# working.net
KiCad netlist of a schematic drawn in EAGLE
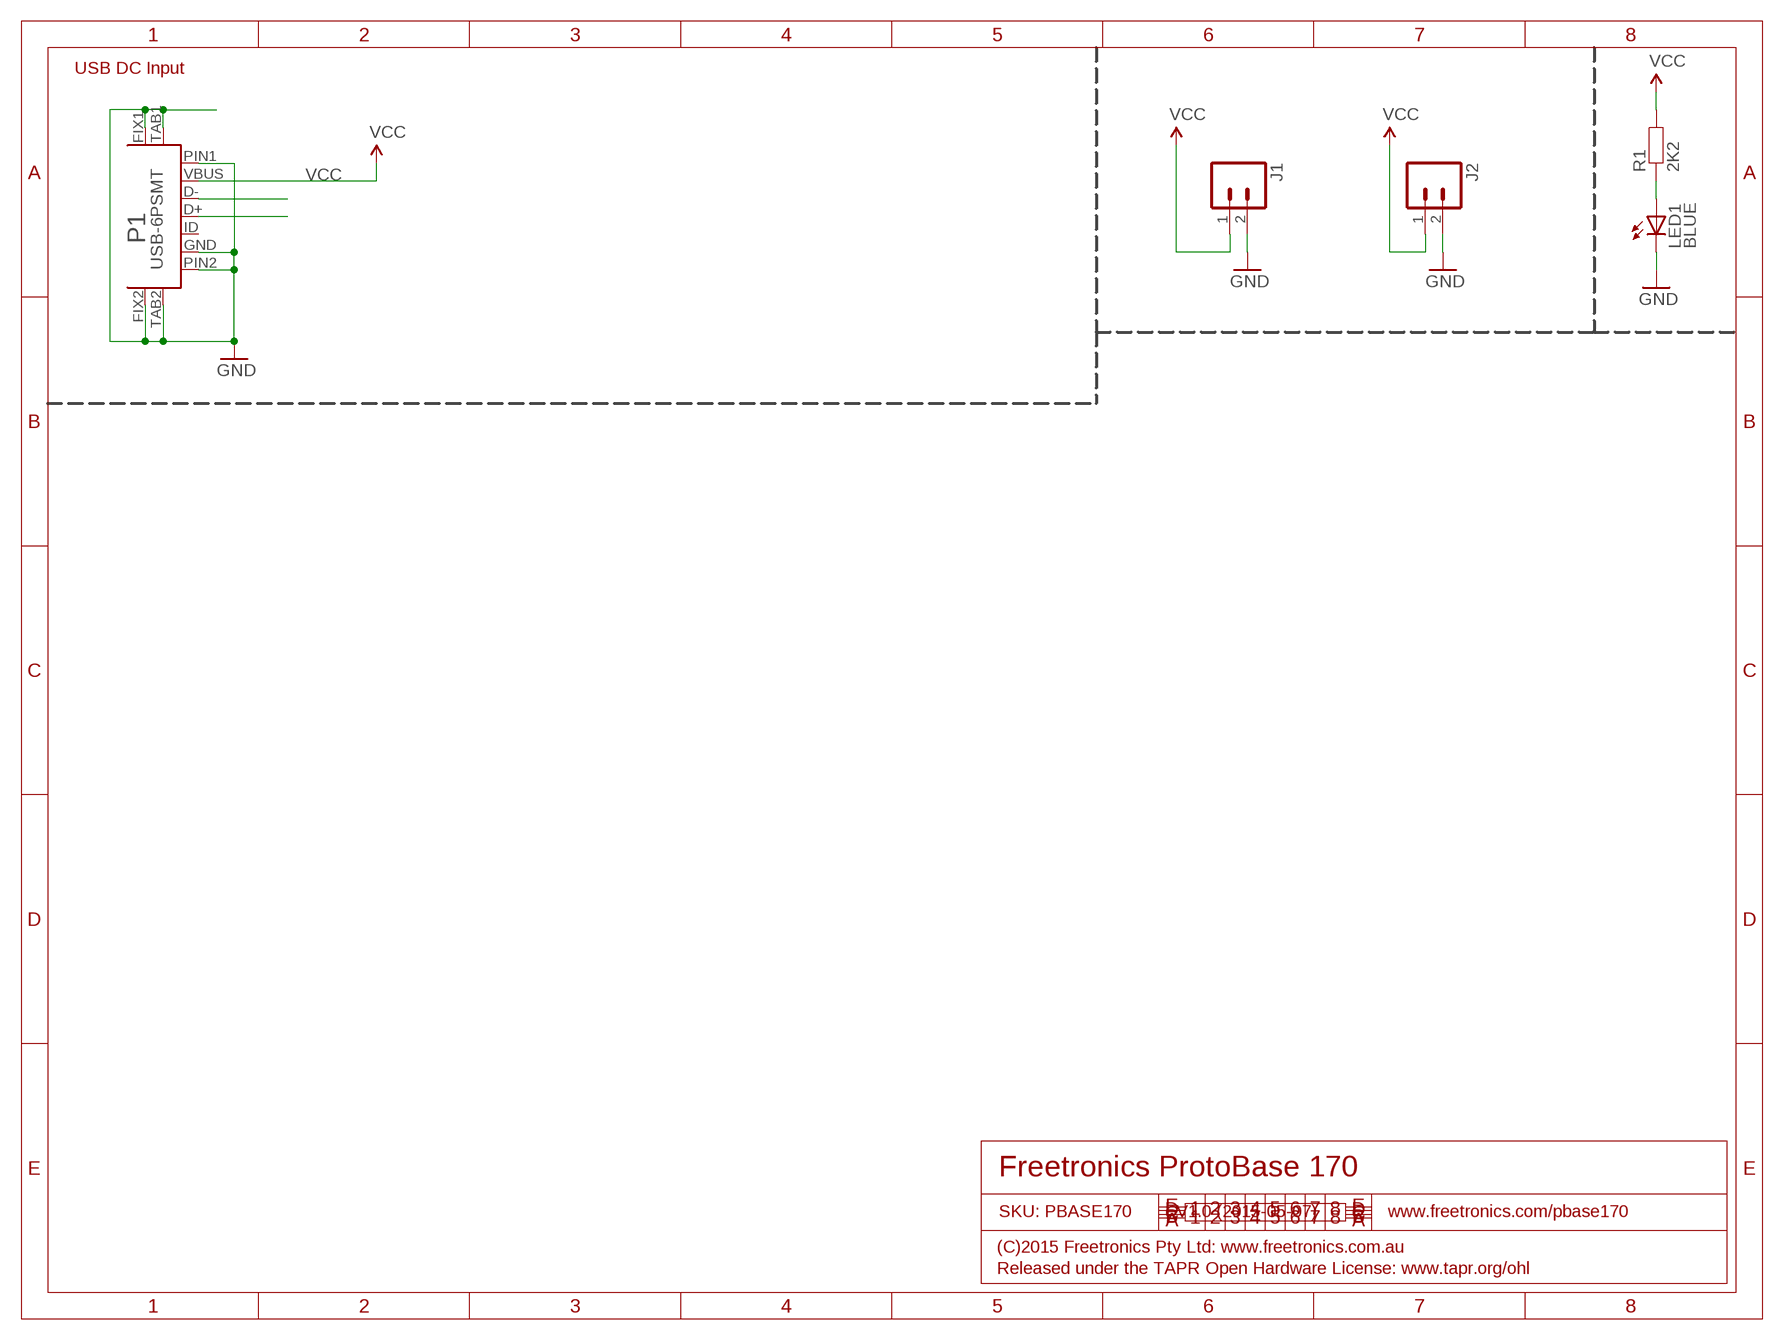
[diagram p0: schematic, sheet 1]

(export (version "E")
  (design (tool "Eeschema 10.0.6"))
  (components
    (comp (ref "J1")
      (value "M02PTH")
      (footprint "eagle-import:1X02")
      (libsource (lib "eagle-import") (part "M02PTH"))
    )
    (comp (ref "J2")
      (value "M02PTH")
      (footprint "eagle-import:1X02")
      (libsource (lib "eagle-import") (part "M02PTH"))
    )
    (comp (ref "LED1")
      (value "BLUE")
      (footprint "eagle-import:LED-0603")
      (libsource (lib "eagle-import") (part "LED0603"))
    )
    (comp (ref "P1")
      (value "USB-6PSMT")
      (footprint "eagle-import:USB-MICROB-MB05PMXX")
      (libsource (lib "eagle-import") (part "USB-6PSMT"))
    )
    (comp (ref "R1")
      (value "2K2")
      (footprint "eagle-import:0603")
      (libsource (lib "eagle-import") (part "RESISTOR0603"))
    )
  )
  (nets
    (net (code "1") (name "GND") (class "Default")
      (node (ref "J1") (pin "2") (pinfunction "2_2") (pintype "passive"))
      (node (ref "J2") (pin "2") (pinfunction "2_2") (pintype "passive"))
      (node (ref "LED1") (pin "C") (pinfunction "C_C") (pintype "passive"))
      (node (ref "P1") (pin "FIX1") (pinfunction "FIX1_FIX1") (pintype "bidirectional"))
      (node (ref "P1") (pin "FIX2") (pinfunction "FIX2_FIX2") (pintype "bidirectional"))
      (node (ref "P1") (pin "GND") (pinfunction "GND_GND") (pintype "bidirectional"))
      (node (ref "P1") (pin "PIN1") (pinfunction "PIN1_PIN1") (pintype "bidirectional"))
      (node (ref "P1") (pin "PIN2") (pinfunction "PIN2_PIN2") (pintype "bidirectional"))
      (node (ref "P1") (pin "TAB1") (pinfunction "TAB1_TAB1") (pintype "bidirectional"))
      (node (ref "P1") (pin "TAB2") (pinfunction "TAB2_TAB2") (pintype "bidirectional"))
    )
    (net (code "2") (name "Net-(LED1-PadA)") (class "Default")
      (node (ref "LED1") (pin "A") (pinfunction "A_A") (pintype "passive"))
      (node (ref "R1") (pin "1") (pinfunction "1_1") (pintype "passive"))
    )
    (net (code "3") (name "VCC") (class "Default")
      (node (ref "J1") (pin "1") (pinfunction "1_1") (pintype "passive"))
      (node (ref "J2") (pin "1") (pinfunction "1_1") (pintype "passive"))
      (node (ref "P1") (pin "VBUS") (pinfunction "VBUS_VBUS") (pintype "bidirectional"))
      (node (ref "R1") (pin "2") (pinfunction "2_2") (pintype "passive"))
    )
    (net (code "4") (name "unconnected-(P1-PadD+)") (class "Default")
      (node (ref "P1") (pin "D+") (pinfunction "D+_D+") (pintype "bidirectional"))
    )
    (net (code "5") (name "unconnected-(P1-PadD-)") (class "Default")
      (node (ref "P1") (pin "D-") (pinfunction "D-_D-") (pintype "bidirectional"))
    )
    (net (code "6") (name "unconnected-(P1-PadID)") (class "Default")
      (node (ref "P1") (pin "ID") (pinfunction "ID_ID") (pintype "bidirectional"))
    )
  )
)
